# relay.net
KiCad netlist of a schematic drawn in Altium Designer
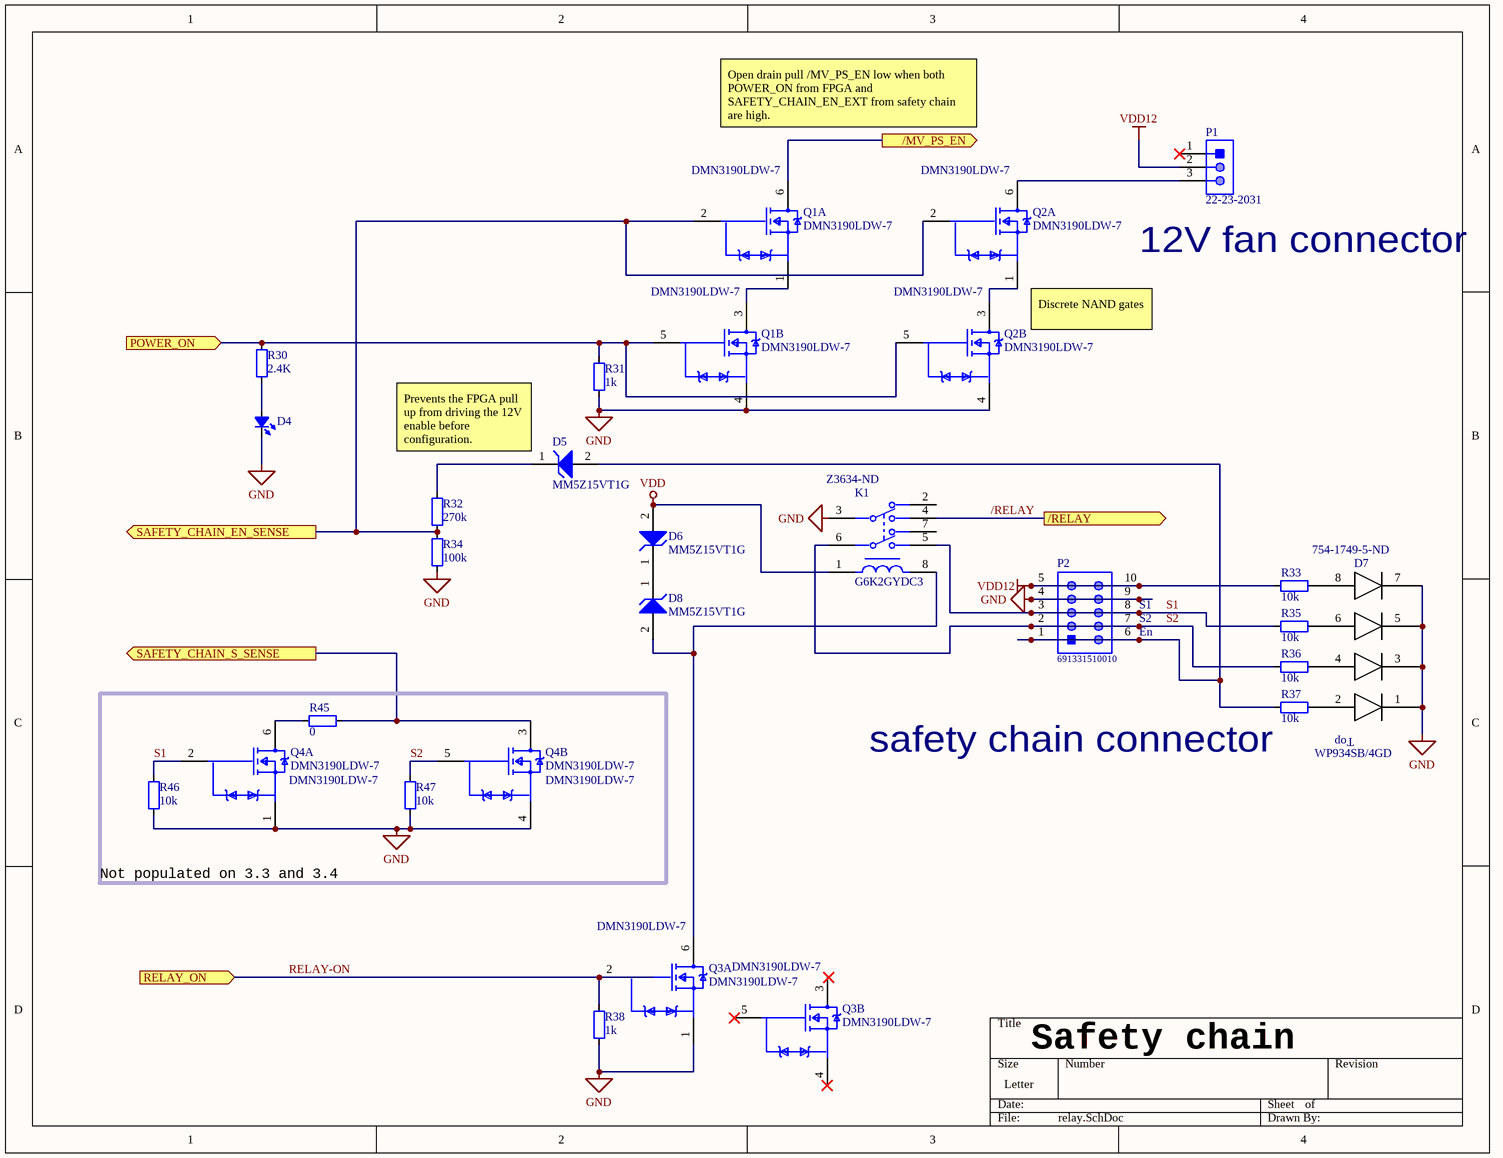
[diagram p0: relay.SchDoc]

(export (version "E")
  (design (tool "Eeschema 10.0.6"))
  (components
    (comp (ref "D4")
      (value "LED_0402")
      (footprint "Components - 10.02.21 - 05.05:ROHM-SML-P11MT_V")
      (description "LED ORANGE CLEAR CHIP SMD")
      (fields
        (field (name "MANUFACTURER") "Kingbright")
        (field (name "MANUFACTURER PART NUMBER") "APHHS1005SECK")
      )
      (libsource (lib "SCH_Active") (part "LED_0402"))
    )
    (comp (ref "D5")
      (value "MM5Z15VT1G")
      (footprint "ONSC-SOD-523-2-502-01_V")
      (description "Zener Voltage Regulator, 500 mW, 2-Pin SOD-523, Pb-Free, Tape and Reel")
      (fields (field (name "MANUFACTURER") "On Semiconductor"))
      (libsource (lib "Altium Content Vault") (part "ONSC-K1A2-2"))
    )
    (comp (ref "D6")
      (value "MM5Z15VT1G")
      (footprint "ONSC-SOD-523-2-502-01_V")
      (description "Zener Voltage Regulator, 500 mW, 2-Pin SOD-523, Pb-Free, Tape and Reel")
      (fields (field (name "MANUFACTURER") "On Semiconductor"))
      (libsource (lib "Altium Content Vault") (part "ONSC-K1A2-2"))
    )
    (comp (ref "D7")
      (value "WP934SB/4GD")
      (footprint "WP934SB/4GD")
      (description "Triple Green T-1 3mm 40° Green Diffused 30 mcd 2.2 V LED Indicator Through Hole")
      (fields
        (field (name "SUPPLIER PART NUMBER 1") "754-1749-5-ND")
        (field (name "MANUFACTURER") "Kingbright")
      )
      (libsource (lib "dvrk-s-pwm") (part "WP934SB/4GD"))
    )
    (comp (ref "D8")
      (value "MM5Z15VT1G")
      (footprint "ONSC-SOD-523-2-502-01_V")
      (description "Zener Voltage Regulator, 500 mW, 2-Pin SOD-523, Pb-Free, Tape and Reel")
      (fields (field (name "MANUFACTURER") "On Semiconductor"))
      (libsource (lib "Altium Content Vault") (part "ONSC-K1A2-2"))
    )
    (comp (ref "K1")
      (value "G6K2GYDC3")
      (footprint "FP-G6K2GYDC3-MFG")
      (description "RELAY TELECOM DPDT 1A 3VDC")
      (fields
        (field (name "SUPPLIER PART NUMBER 1") "Z3634-ND")
        (field (name "MANUFACTURER") "Omron")
        (field (name "MANUFACTURER PART NUMBER") "G6K-2G-Y-DC3")
      )
      (libsource (lib "Altium Content Vault") (part "f6f6c627aadb73ad41e05903558ffa9"))
    )
    (comp (ref "P1")
      (value "22-23-2031")
      (footprint "MOLX-22-23-2031_V")
      (description "Male Header, Pitch 2.54 mm, 1 x 3 Position, Height 8.18 mm, Tail Length 3.56 mm, RoHS, Bulk")
      (fields (field (name "MANUFACTURER") "Molex"))
      (libsource (lib "Altium Content Vault") (part "CN-1P-M-R3"))
    )
    (comp (ref "P2")
      (value "691331510010")
      (footprint "691331510010")
      (description "Serie 3315 - 5.08mm Double Level Horizontal Male PCB Header with Flanges WR-TBL, 10 pin")
      (fields (field (name "MANUFACTURER") "Wurth Elektronik") (field (name "PUBLISHER") "WurthElektronik"))
      (libsource (lib "Altium Content Vault") (part "WE-CN-2P-M-R10_A"))
    )
    (comp (ref "Q1")
      (value "DMN3190LDW-7")
      (footprint "drac_v31:FP-SOT363-IPC_A")
      (description "MOSFET 2N-CH 30V 1A SOT363")
      (fields (field (name "SUPPLIER PART NUMBER 1") "DMN3190LDW-7"))
      (libsource (lib "dvrk-s-pwm_2") (part "a101c64512600b6121a07dee633ff0e"))
    )
    (comp (ref "Q2")
      (value "DMN3190LDW-7")
      (footprint "drac_v31:FP-SOT363-IPC_A")
      (description "MOSFET 2N-CH 30V 1A SOT363")
      (fields (field (name "SUPPLIER PART NUMBER 1") "DMN3190LDW-7"))
      (libsource (lib "dvrk-s-pwm_2") (part "a101c64512600b6121a07dee633ff0e"))
    )
    (comp (ref "Q3")
      (value "DMN3190LDW-7")
      (footprint "drac_v31:FP-SOT363-IPC_A")
      (description "MOSFET 2N-CH 30V 1A SOT363")
      (fields (field (name "SUPPLIER PART NUMBER 1") "DMN3190LDW-7"))
      (libsource (lib "dvrk-s-pwm_2") (part "a101c64512600b6121a07dee633ff0e"))
    )
    (comp (ref "Q4")
      (value "DMN3190LDW-7")
      (footprint "drac_v31:FP-SOT363-IPC_A")
      (description "MOSFET 2N-CH 30V 1A SOT363")
      (fields (field (name "SUPPLIER PART NUMBER 1") "DMN3190LDW-7"))
      (libsource (lib "dvrk-s-pwm_2") (part "a101c64512600b6121a07dee633ff0e"))
    )
    (comp (ref "R30")
      (value "2.4K")
      (footprint "FP-CRCW0402-e3-IPC_B")
      (description "Resistor")
      (fields (field (name "Comment") "Res_0402"))
      (libsource (lib "SCH_Passive") (part "Res_0402"))
    )
    (comp (ref "R31")
      (value "1k")
      (footprint "FP-CRCW0805-HPe3-IPC_B")
      (description "Resistor")
      (fields (field (name "Comment") "Res_0805"))
      (libsource (lib "SCH_Passive") (part "Res_0805"))
    )
    (comp (ref "R32")
      (value "270k")
      (footprint "FP-CRCW0402-e3-IPC_B")
      (description "Resistor")
      (fields (field (name "Comment") "Res_0402"))
      (libsource (lib "SCH_Passive") (part "Res_0402"))
    )
    (comp (ref "R33")
      (value "10k")
      (footprint "FP-CRCW0402-e3-IPC_B")
      (description "Resistor")
      (fields (field (name "Comment") "Res_0402"))
      (libsource (lib "") (part "Res_0402_1"))
    )
    (comp (ref "R34")
      (value "100k")
      (footprint "FP-CRCW0402-e3-IPC_B")
      (description "Resistor")
      (fields (field (name "Comment") "Res_0402"))
      (libsource (lib "SCH_Passive") (part "Res_0402"))
    )
    (comp (ref "R35")
      (value "10k")
      (footprint "FP-CRCW0402-e3-IPC_B")
      (description "Resistor")
      (fields (field (name "Comment") "Res_0402"))
      (libsource (lib "") (part "Res_0402_1"))
    )
    (comp (ref "R36")
      (value "10k")
      (footprint "FP-CRCW0402-e3-IPC_B")
      (description "Resistor")
      (fields (field (name "Comment") "Res_0402"))
      (libsource (lib "") (part "Res_0402_1"))
    )
    (comp (ref "R37")
      (value "10k")
      (footprint "FP-CRCW0402-e3-IPC_B")
      (description "Resistor")
      (fields (field (name "Comment") "Res_0402"))
      (libsource (lib "") (part "Res_0402_1"))
    )
    (comp (ref "R38")
      (value "1k")
      (footprint "FP-CRCW0805-HPe3-IPC_B")
      (description "Resistor")
      (fields (field (name "Comment") "Res_0805"))
      (libsource (lib "SCH_Passive") (part "Res_0805"))
    )
    (comp (ref "R45")
      (value "0")
      (footprint "drac_v31:FP-CRCW0402-e3-IPC_B")
      (description "Resistor")
      (fields (field (name "Comment") "Res_0402"))
      (libsource (lib "") (part "Res_0402_2"))
    )
    (comp (ref "R46")
      (value "10k")
      (footprint "drac_v31:FP-CRCW0402-e3-IPC_B")
      (description "Resistor")
      (fields (field (name "Comment") "Res_0402"))
      (libsource (lib "SCH_Passive") (part "Res_0402"))
    )
    (comp (ref "R47")
      (value "10k")
      (footprint "drac_v31:FP-CRCW0402-e3-IPC_B")
      (description "Resistor")
      (fields (field (name "Comment") "Res_0402"))
      (libsource (lib "SCH_Passive") (part "Res_0402"))
    )
  )
  (nets
    (net (code "1") (name "/POWER_ON") (class "Default")
      (node (ref "Q1") (pin "5") (pinfunction "G2_5") (pintype "passive"))
      (node (ref "Q2") (pin "5") (pinfunction "G2_5") (pintype "passive"))
      (node (ref "R30") (pin "2") (pinfunction "2_2") (pintype "passive"))
      (node (ref "R31") (pin "2") (pinfunction "2_2") (pintype "passive"))
    )
    (net (code "2") (name "/RELAY-ON") (class "Default")
      (node (ref "Q3") (pin "2") (pinfunction "G1_2") (pintype "passive"))
      (node (ref "R38") (pin "2") (pinfunction "2_2") (pintype "passive"))
    )
    (net (code "3") (name "/S1") (class "Default")
      (node (ref "K1") (pin "5") (pinfunction "5_5") (pintype "passive"))
      (node (ref "P2") (pin "3") (pinfunction "3_3") (pintype "passive"))
      (node (ref "P2") (pin "8") (pinfunction "8_8") (pintype "passive"))
      (node (ref "Q4") (pin "2") (pinfunction "G1_2") (pintype "passive"))
      (node (ref "R35") (pin "2") (pinfunction "2_2") (pintype "passive"))
      (node (ref "R46") (pin "2") (pinfunction "2_2") (pintype "passive"))
    )
    (net (code "4") (name "/S2") (class "Default")
      (node (ref "K1") (pin "6") (pinfunction "6_6") (pintype "passive"))
      (node (ref "P2") (pin "2") (pinfunction "2_2") (pintype "passive"))
      (node (ref "P2") (pin "7") (pinfunction "7_7") (pintype "passive"))
      (node (ref "Q4") (pin "5") (pinfunction "G2_5") (pintype "passive"))
      (node (ref "R36") (pin "2") (pinfunction "2_2") (pintype "passive"))
      (node (ref "R47") (pin "2") (pinfunction "2_2") (pintype "passive"))
    )
    (net (code "5") (name "/SAFETY_CHAIN_EN_SENSE") (class "Default")
      (node (ref "Q1") (pin "2") (pinfunction "G1_2") (pintype "passive"))
      (node (ref "Q2") (pin "2") (pinfunction "G1_2") (pintype "passive"))
      (node (ref "R32") (pin "1") (pinfunction "1_1") (pintype "passive"))
      (node (ref "R34") (pin "2") (pinfunction "2_2") (pintype "passive"))
    )
    (net (code "6") (name "/SAFETY_CHAIN_S_SENSE") (class "Default")
      (node (ref "Q4") (pin "3") (pinfunction "D2_3") (pintype "passive"))
      (node (ref "R45") (pin "2") (pinfunction "2_2") (pintype "passive"))
    )
    (net (code "7") (name "/{slash}MV_PS_EN") (class "Default")
      (node (ref "Q1") (pin "6") (pinfunction "D1_6") (pintype "passive"))
    )
    (net (code "8") (name "/{slash}RELAY") (class "Default")
      (node (ref "K1") (pin "4") (pinfunction "4_4") (pintype "passive"))
    )
    (net (code "9") (name "GND") (class "Default")
      (node (ref "D4") (pin "2") (pinfunction "K_2") (pintype "passive"))
      (node (ref "D7") (pin "1") (pintype "passive"))
      (node (ref "D7") (pin "3") (pintype "passive"))
      (node (ref "D7") (pin "5") (pintype "passive"))
      (node (ref "D7") (pin "7") (pintype "passive"))
      (node (ref "K1") (pin "3") (pinfunction "3_3") (pintype "passive"))
      (node (ref "P2") (pin "4") (pinfunction "4_4") (pintype "passive"))
      (node (ref "P2") (pin "9") (pinfunction "9_9") (pintype "passive"))
      (node (ref "Q1") (pin "4") (pinfunction "S2_4") (pintype "passive"))
      (node (ref "Q2") (pin "4") (pinfunction "S2_4") (pintype "passive"))
      (node (ref "Q3") (pin "1") (pinfunction "S1_1") (pintype "passive"))
      (node (ref "Q4") (pin "1") (pinfunction "S1_1") (pintype "passive"))
      (node (ref "Q4") (pin "4") (pinfunction "S2_4") (pintype "passive"))
      (node (ref "R31") (pin "1") (pinfunction "1_1") (pintype "passive"))
      (node (ref "R34") (pin "1") (pinfunction "1_1") (pintype "passive"))
      (node (ref "R38") (pin "1") (pinfunction "1_1") (pintype "passive"))
      (node (ref "R46") (pin "1") (pinfunction "1_1") (pintype "passive"))
      (node (ref "R47") (pin "1") (pinfunction "1_1") (pintype "passive"))
    )
    (net (code "10") (name "Net-(D4-A)") (class "Default")
      (node (ref "D4") (pin "1") (pinfunction "A_1") (pintype "passive"))
      (node (ref "R30") (pin "1") (pinfunction "1_1") (pintype "passive"))
    )
    (net (code "11") (name "Net-(D5-A)") (class "Default")
      (node (ref "D5") (pin "2") (pinfunction "A_2") (pintype "passive"))
      (node (ref "P2") (pin "1") (pinfunction "1_1") (pintype "passive"))
      (node (ref "P2") (pin "6") (pinfunction "6_6") (pintype "passive"))
      (node (ref "R37") (pin "2") (pinfunction "2_2") (pintype "passive"))
    )
    (net (code "12") (name "Net-(D5-K)") (class "Default")
      (node (ref "D5") (pin "1") (pinfunction "K_1") (pintype "passive"))
      (node (ref "R32") (pin "2") (pinfunction "2_2") (pintype "passive"))
    )
    (net (code "13") (name "Net-(D6-K)") (class "Default")
      (node (ref "D6") (pin "1") (pinfunction "K_1") (pintype "passive"))
      (node (ref "D8") (pin "1") (pinfunction "K_1") (pintype "passive"))
    )
    (net (code "14") (name "Net-(D7-Pad2)") (class "Default")
      (node (ref "D7") (pin "2") (pintype "passive"))
      (node (ref "R37") (pin "1") (pinfunction "1_1") (pintype "passive"))
    )
    (net (code "15") (name "Net-(D7-Pad4)") (class "Default")
      (node (ref "D7") (pin "4") (pintype "passive"))
      (node (ref "R36") (pin "1") (pinfunction "1_1") (pintype "passive"))
    )
    (net (code "16") (name "Net-(D7-Pad6)") (class "Default")
      (node (ref "D7") (pin "6") (pintype "passive"))
      (node (ref "R35") (pin "1") (pinfunction "1_1") (pintype "passive"))
    )
    (net (code "17") (name "Net-(D7-Pad8)") (class "Default")
      (node (ref "D7") (pin "8") (pintype "passive"))
      (node (ref "R33") (pin "1") (pinfunction "1_1") (pintype "passive"))
    )
    (net (code "18") (name "Net-(D8-A)") (class "Default")
      (node (ref "D8") (pin "2") (pinfunction "A_2") (pintype "passive"))
      (node (ref "K1") (pin "8") (pinfunction "8_8") (pintype "passive"))
      (node (ref "Q3") (pin "6") (pinfunction "D1_6") (pintype "passive"))
    )
    (net (code "19") (name "Net-(Q1A-S1)") (class "Default")
      (node (ref "Q1") (pin "1") (pinfunction "S1_1") (pintype "passive"))
      (node (ref "Q1") (pin "3") (pinfunction "D2_3") (pintype "passive"))
    )
    (net (code "20") (name "Net-(Q2A-D1)") (class "Default")
      (node (ref "P1") (pin "3") (pinfunction "3_3") (pintype "passive"))
      (node (ref "Q2") (pin "6") (pinfunction "D1_6") (pintype "passive"))
    )
    (net (code "21") (name "Net-(Q2A-S1)") (class "Default")
      (node (ref "Q2") (pin "1") (pinfunction "S1_1") (pintype "passive"))
      (node (ref "Q2") (pin "3") (pinfunction "D2_3") (pintype "passive"))
    )
    (net (code "22") (name "Net-(Q4A-D1)") (class "Default")
      (node (ref "Q4") (pin "6") (pinfunction "D1_6") (pintype "passive"))
      (node (ref "R45") (pin "1") (pinfunction "1_1") (pintype "passive"))
    )
    (net (code "23") (name "VDD") (class "Default")
      (node (ref "D6") (pin "2") (pinfunction "A_2") (pintype "passive"))
      (node (ref "K1") (pin "1") (pinfunction "1_1") (pintype "passive"))
    )
    (net (code "24") (name "VDD12") (class "Default")
      (node (ref "P1") (pin "2") (pinfunction "2_2") (pintype "passive"))
      (node (ref "P2") (pin "10") (pinfunction "10_10") (pintype "passive"))
      (node (ref "P2") (pin "5") (pinfunction "5_5") (pintype "passive"))
      (node (ref "R33") (pin "2") (pinfunction "2_2") (pintype "passive"))
    )
    (net (code "25") (name "unconnected-(K1-Pad2)") (class "Default")
      (node (ref "K1") (pin "2") (pinfunction "2_2") (pintype "passive"))
    )
    (net (code "26") (name "unconnected-(K1-Pad7)") (class "Default")
      (node (ref "K1") (pin "7") (pinfunction "7_7") (pintype "passive"))
    )
    (net (code "27") (name "unconnected-(P1-Pad1)") (class "Default")
      (node (ref "P1") (pin "1") (pinfunction "1_1") (pintype "passive+no_connect"))
    )
    (net (code "28") (name "unconnected-(Q3B-D2-Pad3)") (class "Default")
      (node (ref "Q3") (pin "3") (pinfunction "D2_3") (pintype "passive"))
    )
    (net (code "29") (name "unconnected-(Q3B-G2-Pad5)") (class "Default")
      (node (ref "Q3") (pin "5") (pinfunction "G2_5") (pintype "passive+no_connect"))
    )
    (net (code "30") (name "unconnected-(Q3B-S2-Pad4)") (class "Default")
      (node (ref "Q3") (pin "4") (pinfunction "S2_4") (pintype "passive+no_connect"))
    )
  )
)
